# GSM_GPS.net
KiCad netlist of a schematic drawn in Altium Designer
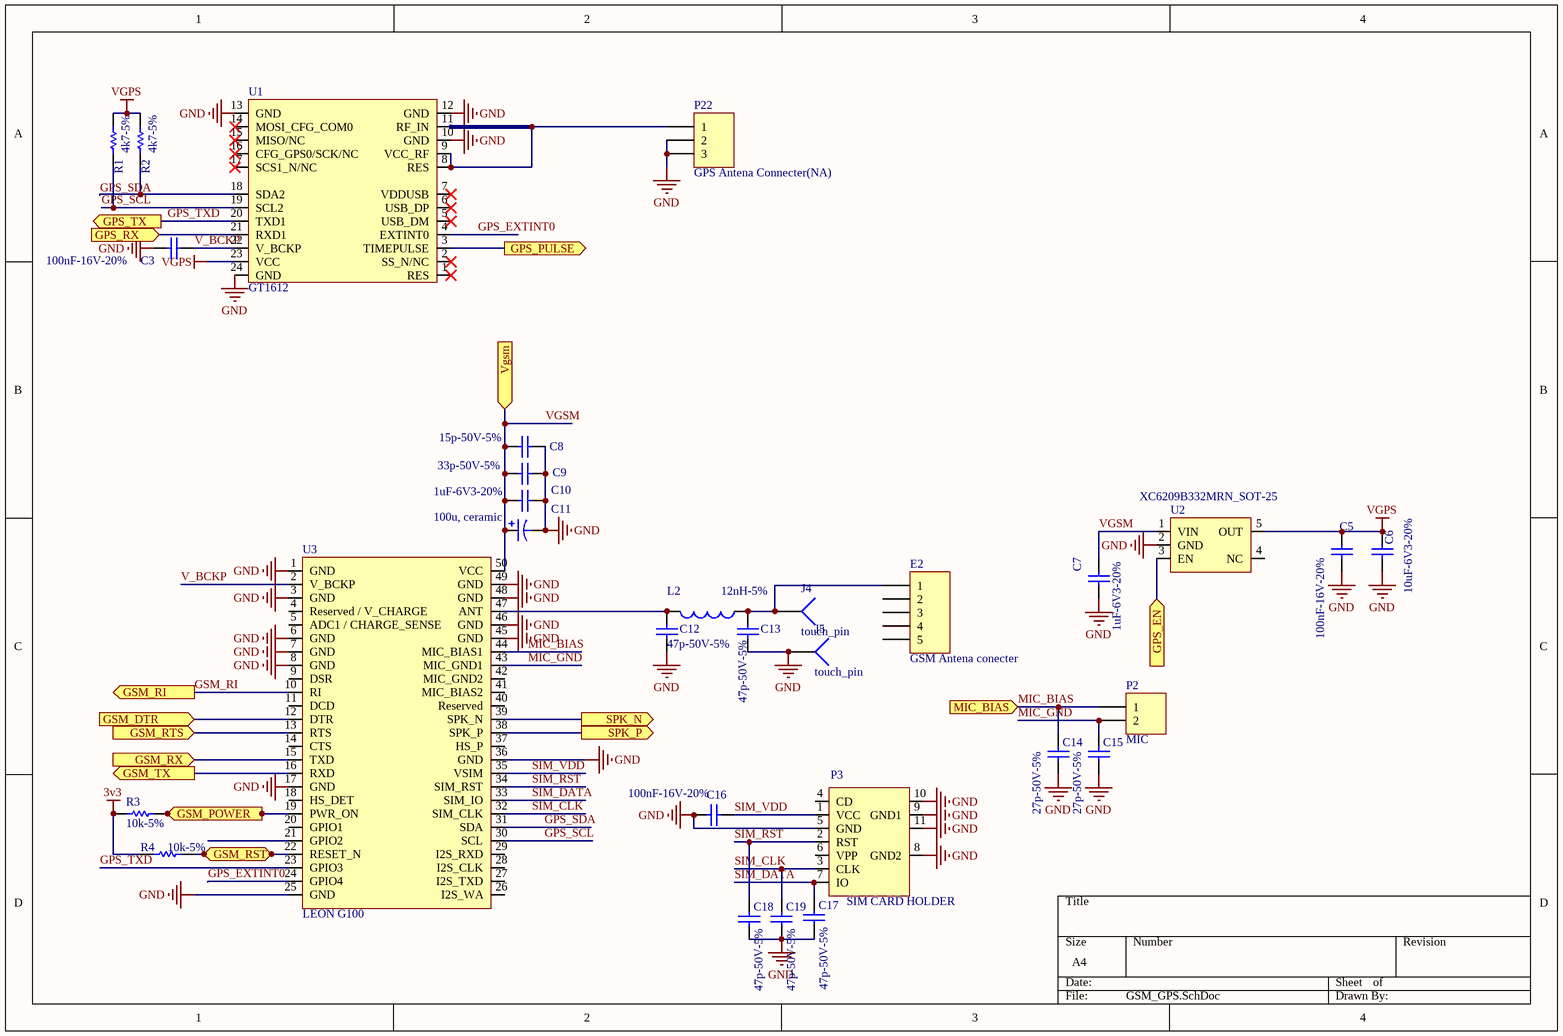
[diagram p0: GSM_GPS.SchDoc]

(export (version "E")
  (design (tool "Eeschema 10.0.6"))
  (components
    (comp (ref "C3")
      (value "100nF-16V-20%")
      (footprint "C0402")
      (description "CAP CER 0.1UF 16V Y5V 0402")
      (fields
        (field (name "MANUFACTURER") "Yageo")
        (field (name "DIGI-KEY PART NUMBER") "311-1047-1-ND")
        (field (name "PUBLISHER") "Altium Limited")
      )
      (libsource (lib "Miscellaneous Devices") (part "Cap"))
    )
    (comp (ref "C5")
      (value "100nF-16V-20%")
      (footprint "C0402")
      (description "CAP CER 0.1UF 16V Y5V 0402")
      (fields
        (field (name "MANUFACTURER") "Yageo")
        (field (name "DIGI-KEY PART NUMBER") "311-1047-1-ND")
        (field (name "PUBLISHER") "Altium Limited")
      )
      (libsource (lib "Miscellaneous Devices") (part "Cap"))
    )
    (comp (ref "C6")
      (value "10uF-6V3-20%")
      (footprint "C0603")
      (description "CAP CER 10UF 6.3V 20% X5R 0603")
      (fields
        (field (name "MANUFACTURER") "Murata Electronics North America")
        (field (name "DIGI-KEY PART NUMBER") "490-3896-1-ND")
        (field (name "PUBLISHER") "Altium Limited")
      )
      (libsource (lib "Miscellaneous Devices") (part "Cap"))
    )
    (comp (ref "C7")
      (value "1uF-6V3-20%")
      (footprint "C0402")
      (description "CAP CER 1UF 6.3V Y5V 0402")
      (fields
        (field (name "MANUFACTURER") "Yageo")
        (field (name "DIGI-KEY PART NUMBER") "311-1377-2-ND")
        (field (name "PUBLISHER") "Altium Limited")
      )
      (libsource (lib "Miscellaneous Devices") (part "Cap"))
    )
    (comp (ref "C8")
      (value "15p-50V-5%")
      (footprint "C0402")
      (description "CAP CER 15PF 50V 5% NPO 0402")
      (fields
        (field (name "MANUFACTURER") "Yageo")
        (field (name "DIGI-KEY PART NUMBER") "311-1017-1-ND")
        (field (name "PUBLISHER") "Altium Limited")
      )
      (libsource (lib "Miscellaneous Devices") (part "Cap"))
    )
    (comp (ref "C9")
      (value "33p-50V-5%")
      (footprint "C0402")
      (description "CAP CER 33PF 50V 5% NPO 0402")
      (fields
        (field (name "MANUFACTURER") "Yageo")
        (field (name "DIGI-KEY PART NUMBER") "311-1020-1-ND")
        (field (name "PUBLISHER") "Altium Limited")
      )
      (libsource (lib "Miscellaneous Devices") (part "Cap"))
    )
    (comp (ref "C10")
      (value "1uF-6V3-20%")
      (footprint "C0402")
      (description "CAP CER 1UF 6.3V Y5V 0402")
      (fields
        (field (name "MANUFACTURER") "Yageo")
        (field (name "DIGI-KEY PART NUMBER") "311-1377-2-ND")
        (field (name "PUBLISHER") "Altium Limited")
      )
      (libsource (lib "Miscellaneous Devices") (part "Cap"))
    )
    (comp (ref "C11")
      (value "100u, ceramic")
      (footprint "C1210")
      (description "CAP CER 100UF 10V 20% X5R 1812")
      (fields
        (field (name "DIGI-KEY PART NUMBER") "445-7743-2-ND")
        (field (name "MANUFACTURER PART NUMBER") "C4532X5R1A107M")
        (field (name "PUBLISHER") "Altium Limited")
      )
      (libsource (lib "Miscellaneous Devices") (part "Cap Pol3"))
    )
    (comp (ref "C12")
      (value "47p-50V-5%")
      (footprint "C0402")
      (description "CAP CER 47PF 50V 5% NPO 0402")
      (fields
        (field (name "MANUFACTURER") "Yageo")
        (field (name "DIGI-KEY PART NUMBER") "311-1021-1-ND")
        (field (name "PUBLISHER") "Altium Limited")
      )
      (libsource (lib "Miscellaneous Devices") (part "Cap"))
    )
    (comp (ref "C13")
      (value "47p-50V-5%")
      (footprint "C0402")
      (description "CAP CER 47PF 50V 5% NPO 0402")
      (fields
        (field (name "MANUFACTURER") "Yageo")
        (field (name "DIGI-KEY PART NUMBER") "311-1021-1-ND")
        (field (name "PUBLISHER") "Altium Limited")
      )
      (libsource (lib "Miscellaneous Devices") (part "Cap"))
    )
    (comp (ref "C14")
      (value "27p-50V-5%")
      (footprint "C0402")
      (description "CAP CER 27PF 50V 5% NPO 0402")
      (fields
        (field (name "MANUFACTURER") "Yageo")
        (field (name "DIGI-KEY PART NUMBER") "311-1019-2-ND")
        (field (name "PUBLISHER") "Altium Limited")
      )
      (libsource (lib "Miscellaneous Devices") (part "Cap"))
    )
    (comp (ref "C15")
      (value "27p-50V-5%")
      (footprint "C0402")
      (description "CAP CER 27PF 50V 5% NPO 0402")
      (fields
        (field (name "MANUFACTURER") "Yageo")
        (field (name "DIGI-KEY PART NUMBER") "311-1019-2-ND")
        (field (name "PUBLISHER") "Altium Limited")
      )
      (libsource (lib "Miscellaneous Devices") (part "Cap"))
    )
    (comp (ref "C16")
      (value "100nF-16V-20%")
      (footprint "C0402")
      (description "CAP CER 0.1UF 16V Y5V 0402")
      (fields
        (field (name "MANUFACTURER") "Yageo")
        (field (name "DIGI-KEY PART NUMBER") "311-1047-1-ND")
        (field (name "PUBLISHER") "Altium Limited")
      )
      (libsource (lib "Miscellaneous Devices") (part "Cap"))
    )
    (comp (ref "C17")
      (value "47p-50V-5%")
      (footprint "C0402")
      (description "CAP CER 47PF 50V 5% NPO 0402")
      (fields
        (field (name "MANUFACTURER") "Yageo")
        (field (name "DIGI-KEY PART NUMBER") "311-1021-1-ND")
        (field (name "PUBLISHER") "Altium Limited")
      )
      (libsource (lib "Miscellaneous Devices") (part "Cap"))
    )
    (comp (ref "C18")
      (value "47p-50V-5%")
      (footprint "C0402")
      (description "CAP CER 47PF 50V 5% NPO 0402")
      (fields
        (field (name "MANUFACTURER") "Yageo")
        (field (name "DIGI-KEY PART NUMBER") "311-1021-1-ND")
        (field (name "PUBLISHER") "Altium Limited")
      )
      (libsource (lib "Miscellaneous Devices") (part "Cap"))
    )
    (comp (ref "C19")
      (value "47p-50V-5%")
      (footprint "C0402")
      (description "CAP CER 47PF 50V 5% NPO 0402")
      (fields
        (field (name "MANUFACTURER") "Yageo")
        (field (name "DIGI-KEY PART NUMBER") "311-1021-1-ND")
        (field (name "PUBLISHER") "Altium Limited")
      )
      (libsource (lib "Miscellaneous Devices") (part "Cap"))
    )
    (comp (ref "E2")
      (value "GSM Antena conecter")
      (footprint "A10343-GSM850/900/1800/1900/WCDMA")
      (description "Header, 5-Pin")
      (fields (field (name "PUBLISHER") "Altium Limited"))
      (libsource (lib "Miscellaneous Connectors") (part "Header 5"))
    )
    (comp (ref "J4")
      (value "touch_pin")
      (footprint "TOUCH_PIN")
      (description "Socket")
      (fields (field (name "PUBLISHER") "Altium Limited"))
      (libsource (lib "Miscellaneous Connectors") (part "Socket"))
    )
    (comp (ref "J5")
      (value "touch_pin")
      (footprint "TOUCH_PIN")
      (description "Socket")
      (fields (field (name "PUBLISHER") "Altium Limited"))
      (libsource (lib "Miscellaneous Connectors") (part "Socket"))
    )
    (comp (ref "L2")
      (value "12nH-5%")
      (footprint "R0402")
      (description "INDUCTOR 12NH 300MA 0402")
      (fields
        (field (name "DIGI-KEY PART NUMBER") "490-2624-2-ND")
        (field (name "MANUFACTURER") "Murata Electronics North America")
        (field (name "PUBLISHER") "Altium Limited")
      )
      (libsource (lib "Miscellaneous Devices") (part "Inductor"))
    )
    (comp (ref "P2")
      (value "MIC")
      (footprint "HEADER_1.27mm_2PIN")
      (description "Header, 2-Pin")
      (fields (field (name "PUBLISHER") "Altium Limited"))
      (libsource (lib "Miscellaneous Connectors") (part "Header 2"))
    )
    (comp (ref "P3")
      (value "SIM CARD HOLDER")
      (footprint "MICRO_SIM_SOCKET")
      (description "SIM _CONNECTOR_410108105011-2LF")
      (fields (field (name "MANUFACTURER") "Tyrone"))
      (libsource (lib "Schlib1") (part "SIM CARD"))
    )
    (comp (ref "P22")
      (value "GPS Antena Connecter(NA)")
      (footprint "IPX SMD PCB Plug")
      (description "GPS Antena")
      (fields (field (name "PUBLISHER") "Altium Limited"))
      (libsource (lib "Miscellaneous Connectors") (part "Header 3"))
    )
    (comp (ref "R1")
      (value "4k7-5%")
      (footprint "R0402")
      (description "RES 4.7K OHM 1/16W 5% 0402 SMD")
      (fields
        (field (name "DIGI-KEY PART NUMBER") "311-4.7KJRCT-ND")
        (field (name "MANUFACTURER") "Yageo")
        (field (name "PUBLISHER") "Altium Limited")
      )
      (libsource (lib "Miscellaneous Devices") (part "Res1"))
    )
    (comp (ref "R2")
      (value "4k7-5%")
      (footprint "R0402")
      (description "RES 4.7K OHM 1/16W 5% 0402 SMD")
      (fields
        (field (name "DIGI-KEY PART NUMBER") "311-4.7KJRCT-ND")
        (field (name "MANUFACTURER") "Yageo")
        (field (name "PUBLISHER") "Altium Limited")
      )
      (libsource (lib "Miscellaneous Devices") (part "Res1"))
    )
    (comp (ref "R3")
      (value "10k-5%")
      (footprint "R0402")
      (description "RES 10K OHM 1/16W 5% 0402 SMD")
      (fields
        (field (name "DIGI-KEY PART NUMBER") "311-10KJRCT-ND")
        (field (name "MANUFACTURER") "Yageo")
        (field (name "PUBLISHER") "Altium Limited")
      )
      (libsource (lib "Miscellaneous Devices") (part "Res1"))
    )
    (comp (ref "R4")
      (value "10k-5%")
      (footprint "R0402")
      (description "RES 10K OHM 1/16W 5% 0402 SMD")
      (fields
        (field (name "DIGI-KEY PART NUMBER") "311-10KJRCT-ND")
        (field (name "MANUFACTURER") "Yageo")
        (field (name "PUBLISHER") "Altium Limited")
      )
      (libsource (lib "Miscellaneous Devices") (part "Res1"))
    )
    (comp (ref "U1") (value "GT1612") (footprint "GT1612") (libsource (lib "Schlib1") (part "GPS-GT1612")))
    (comp (ref "U2")
      (value "XC6209B332MRN_SOT-25")
      (footprint "SOT23-5")
      (fields (field (name "MANUFACTURER") "Tyrone"))
      (libsource (lib "Schlib1") (part "XC6209B332MRN_SOT-25"))
    )
    (comp (ref "U3")
      (value "LEON G100")
      (footprint "U-BLOX-G100")
      (fields (field (name "MANUFACTURER") "Tyrone"))
      (libsource (lib "gsm_module") (part "ublox"))
    )
  )
  (nets
    (net (code "1") (name "/GPS_EN") (class "Default")
      (node (ref "U2") (pin "3") (pinfunction "EN_3") (pintype "passive"))
    )
    (net (code "2") (name "/GPS_EXTINT0") (class "Default")
      (node (ref "U1") (pin "4") (pinfunction "EXTINT0_4") (pintype "passive"))
      (node (ref "U3") (pin "24") (pinfunction "GPIO4_24") (pintype "passive"))
    )
    (net (code "3") (name "/GPS_PULSE") (class "Default")
      (node (ref "U1") (pin "3") (pinfunction "TIMEPULSE_3") (pintype "passive"))
    )
    (net (code "4") (name "/GPS_RX") (class "Default")
      (node (ref "U1") (pin "21") (pinfunction "RXD1_21") (pintype "passive"))
    )
    (net (code "5") (name "/GPS_SCL") (class "Default")
      (node (ref "R1") (pin "1") (pinfunction "1_1") (pintype "passive"))
      (node (ref "U1") (pin "19") (pinfunction "SCL2_19") (pintype "passive"))
      (node (ref "U3") (pin "30") (pinfunction "SCL_30") (pintype "passive"))
    )
    (net (code "6") (name "/GPS_SDA") (class "Default")
      (node (ref "R2") (pin "1") (pinfunction "1_1") (pintype "passive"))
      (node (ref "U1") (pin "18") (pinfunction "SDA2_18") (pintype "passive"))
      (node (ref "U3") (pin "31") (pinfunction "SDA_31") (pintype "passive"))
    )
    (net (code "7") (name "/GPS_TXD") (class "Default")
      (node (ref "U1") (pin "20") (pinfunction "TXD1_20") (pintype "passive"))
      (node (ref "U3") (pin "23") (pinfunction "GPIO3_23") (pintype "passive"))
    )
    (net (code "8") (name "/GSM_DTR") (class "Default")
      (node (ref "U3") (pin "12") (pinfunction "DTR_12") (pintype "passive"))
    )
    (net (code "9") (name "/GSM_POWER") (class "Default")
      (node (ref "R3") (pin "2") (pinfunction "2_2") (pintype "passive"))
      (node (ref "U3") (pin "19") (pinfunction "PWR_ON_19") (pintype "passive"))
    )
    (net (code "10") (name "/GSM_RI") (class "Default")
      (node (ref "U3") (pin "10") (pinfunction "RI_10") (pintype "passive"))
    )
    (net (code "11") (name "/GSM_RST") (class "Default")
      (node (ref "R4") (pin "2") (pinfunction "2_2") (pintype "passive"))
      (node (ref "U3") (pin "22") (pinfunction "RESET_N_22") (pintype "passive"))
    )
    (net (code "12") (name "/GSM_RTS") (class "Default")
      (node (ref "U3") (pin "13") (pinfunction "RTS_13") (pintype "passive"))
    )
    (net (code "13") (name "/GSM_RX") (class "Default")
      (node (ref "U3") (pin "15") (pinfunction "TXD_15") (pintype "passive"))
    )
    (net (code "14") (name "/GSM_TX") (class "Default")
      (node (ref "U3") (pin "16") (pinfunction "RXD_16") (pintype "passive"))
    )
    (net (code "15") (name "/MIC_BIAS") (class "Default")
      (node (ref "C14") (pin "2") (pinfunction "2_2") (pintype "passive"))
      (node (ref "P2") (pin "1") (pinfunction "1_1") (pintype "passive"))
      (node (ref "U3") (pin "44") (pinfunction "MIC_BIAS1_44") (pintype "passive"))
    )
    (net (code "16") (name "/MIC_GND") (class "Default")
      (node (ref "C15") (pin "2") (pinfunction "2_2") (pintype "passive"))
      (node (ref "P2") (pin "2") (pinfunction "2_2") (pintype "passive"))
      (node (ref "U3") (pin "43") (pinfunction "MIC_GND1_43") (pintype "passive"))
    )
    (net (code "17") (name "/SIM_CLK") (class "Default")
      (node (ref "C19") (pin "2") (pinfunction "2_2") (pintype "passive"))
      (node (ref "P3") (pin "3") (pinfunction "CLK_3") (pintype "passive"))
      (node (ref "U3") (pin "32") (pinfunction "SIM_CLK_32") (pintype "passive"))
    )
    (net (code "18") (name "/SIM_DATA") (class "Default")
      (node (ref "C17") (pin "2") (pinfunction "2_2") (pintype "passive"))
      (node (ref "P3") (pin "7") (pinfunction "IO_7") (pintype "passive"))
      (node (ref "U3") (pin "33") (pinfunction "SIM_IO_33") (pintype "passive"))
    )
    (net (code "19") (name "/SIM_RST") (class "Default")
      (node (ref "C18") (pin "2") (pinfunction "2_2") (pintype "passive"))
      (node (ref "P3") (pin "2") (pinfunction "RST_2") (pintype "passive"))
      (node (ref "U3") (pin "34") (pinfunction "SIM_RST_34") (pintype "passive"))
    )
    (net (code "20") (name "/SIM_VDD") (class "Default")
      (node (ref "C16") (pin "1") (pinfunction "1_1") (pintype "passive"))
      (node (ref "P3") (pin "1") (pinfunction "VCC_1") (pintype "passive"))
      (node (ref "U3") (pin "35") (pinfunction "VSIM_35") (pintype "passive"))
    )
    (net (code "21") (name "/SPK_N") (class "Default")
      (node (ref "U3") (pin "39") (pinfunction "SPK_N_39") (pintype "passive"))
    )
    (net (code "22") (name "/SPK_P") (class "Default")
      (node (ref "U3") (pin "38") (pinfunction "SPK_P_38") (pintype "passive"))
    )
    (net (code "23") (name "/VGSM") (class "Default")
      (node (ref "C10") (pin "2") (pinfunction "2_2") (pintype "passive"))
      (node (ref "C11") (pin "1") (pinfunction "1_1") (pintype "passive"))
      (node (ref "C7") (pin "2") (pinfunction "2_2") (pintype "passive"))
      (node (ref "C8") (pin "1") (pinfunction "1_1") (pintype "passive"))
      (node (ref "C9") (pin "1") (pinfunction "1_1") (pintype "passive"))
      (node (ref "U2") (pin "1") (pinfunction "VIN_1") (pintype "passive"))
      (node (ref "U3") (pin "50") (pinfunction "VCC_50") (pintype "passive"))
    )
    (net (code "24") (name "/V_BCKP") (class "Default")
      (node (ref "C3") (pin "2") (pinfunction "2_2") (pintype "passive"))
      (node (ref "U1") (pin "22") (pinfunction "V_BCKP_22") (pintype "passive"))
      (node (ref "U3") (pin "2") (pinfunction "V_BCKP_2") (pintype "passive"))
    )
    (net (code "25") (name "3v3") (class "Default")
      (node (ref "R3") (pin "1") (pinfunction "1_1") (pintype "passive"))
      (node (ref "R4") (pin "1") (pinfunction "1_1") (pintype "passive"))
    )
    (net (code "26") (name "GND") (class "Default")
      (node (ref "C10") (pin "1") (pinfunction "1_1") (pintype "passive"))
      (node (ref "C11") (pin "2") (pinfunction "2_2") (pintype "passive"))
      (node (ref "C12") (pin "1") (pinfunction "1_1") (pintype "passive"))
      (node (ref "C13") (pin "1") (pinfunction "1_1") (pintype "passive"))
      (node (ref "C14") (pin "1") (pinfunction "1_1") (pintype "passive"))
      (node (ref "C15") (pin "1") (pinfunction "1_1") (pintype "passive"))
      (node (ref "C16") (pin "2") (pinfunction "2_2") (pintype "passive"))
      (node (ref "C17") (pin "1") (pinfunction "1_1") (pintype "passive"))
      (node (ref "C18") (pin "1") (pinfunction "1_1") (pintype "passive"))
      (node (ref "C19") (pin "1") (pinfunction "1_1") (pintype "passive"))
      (node (ref "C3") (pin "1") (pinfunction "1_1") (pintype "passive"))
      (node (ref "C5") (pin "1") (pinfunction "1_1") (pintype "passive"))
      (node (ref "C6") (pin "1") (pinfunction "1_1") (pintype "passive"))
      (node (ref "C7") (pin "1") (pinfunction "1_1") (pintype "passive"))
      (node (ref "C8") (pin "2") (pinfunction "2_2") (pintype "passive"))
      (node (ref "C9") (pin "2") (pinfunction "2_2") (pintype "passive"))
      (node (ref "J5") (pin "1") (pinfunction "1_1") (pintype "passive"))
      (node (ref "P22") (pin "2") (pinfunction "2_2") (pintype "passive"))
      (node (ref "P22") (pin "3") (pinfunction "3_3") (pintype "passive"))
      (node (ref "P3") (pin "10") (pinfunction "GND3_10") (pintype "passive"))
      (node (ref "P3") (pin "11") (pinfunction "GND4_11") (pintype "passive"))
      (node (ref "P3") (pin "5") (pinfunction "GND_5") (pintype "passive"))
      (node (ref "P3") (pin "8") (pinfunction "GND2_8") (pintype "passive"))
      (node (ref "P3") (pin "9") (pinfunction "GND1_9") (pintype "passive"))
      (node (ref "U1") (pin "10") (pinfunction "GND_10") (pintype "passive"))
      (node (ref "U1") (pin "12") (pinfunction "GND_12") (pintype "passive"))
      (node (ref "U1") (pin "13") (pinfunction "GND_13") (pintype "passive"))
      (node (ref "U1") (pin "24") (pinfunction "GND_24") (pintype "passive"))
      (node (ref "U2") (pin "2") (pinfunction "GND_2") (pintype "passive"))
      (node (ref "U3") (pin "1") (pinfunction "GND_1") (pintype "passive"))
      (node (ref "U3") (pin "17") (pinfunction "GND_17") (pintype "passive"))
      (node (ref "U3") (pin "25") (pinfunction "GND_25") (pintype "passive"))
      (node (ref "U3") (pin "3") (pinfunction "GND_3") (pintype "passive"))
      (node (ref "U3") (pin "36") (pinfunction "GND_36") (pintype "passive"))
      (node (ref "U3") (pin "45") (pinfunction "GND_45") (pintype "passive"))
      (node (ref "U3") (pin "46") (pinfunction "GND_46") (pintype "passive"))
      (node (ref "U3") (pin "48") (pinfunction "GND_48") (pintype "passive"))
      (node (ref "U3") (pin "49") (pinfunction "GND_49") (pintype "passive"))
      (node (ref "U3") (pin "6") (pinfunction "GND_6") (pintype "passive"))
      (node (ref "U3") (pin "7") (pinfunction "GND_7") (pintype "passive"))
      (node (ref "U3") (pin "8") (pinfunction "GND_8") (pintype "passive"))
    )
    (net (code "27") (name "Net-(C13-Pad2)") (class "Default")
      (node (ref "C13") (pin "2") (pinfunction "2_2") (pintype "passive"))
      (node (ref "E2") (pin "1") (pinfunction "1_1") (pintype "passive"))
      (node (ref "J4") (pin "1") (pinfunction "1_1") (pintype "passive"))
      (node (ref "L2") (pin "1") (pinfunction "1_1") (pintype "passive"))
    )
    (net (code "28") (name "Net-(U1-RF_IN)") (class "Default")
      (node (ref "P22") (pin "1") (pinfunction "1_1") (pintype "passive"))
      (node (ref "U1") (pin "11") (pinfunction "RF_IN_11") (pintype "passive"))
      (node (ref "U1") (pin "8") (pinfunction "RES_8") (pintype "passive"))
      (node (ref "U1") (pin "9") (pinfunction "VCC_RF_9") (pintype "passive"))
    )
    (net (code "29") (name "Net-(U3-ANT)") (class "Default")
      (node (ref "C12") (pin "2") (pinfunction "2_2") (pintype "passive"))
      (node (ref "L2") (pin "2") (pinfunction "2_2") (pintype "passive"))
      (node (ref "U3") (pin "47") (pinfunction "ANT_47") (pintype "passive"))
    )
    (net (code "30") (name "VGPS") (class "Default")
      (node (ref "C5") (pin "2") (pinfunction "2_2") (pintype "passive"))
      (node (ref "C6") (pin "2") (pinfunction "2_2") (pintype "passive"))
      (node (ref "R1") (pin "2") (pinfunction "2_2") (pintype "passive"))
      (node (ref "R2") (pin "2") (pinfunction "2_2") (pintype "passive"))
      (node (ref "U1") (pin "23") (pinfunction "VCC_23") (pintype "passive"))
      (node (ref "U2") (pin "5") (pinfunction "OUT_5") (pintype "passive"))
    )
    (net (code "31") (name "unconnected-(E2-Pad2)") (class "Default")
      (node (ref "E2") (pin "2") (pinfunction "2_2") (pintype "passive"))
    )
    (net (code "32") (name "unconnected-(E2-Pad3)") (class "Default")
      (node (ref "E2") (pin "3") (pinfunction "3_3") (pintype "passive"))
    )
    (net (code "33") (name "unconnected-(E2-Pad4)") (class "Default")
      (node (ref "E2") (pin "4") (pinfunction "4_4") (pintype "passive"))
    )
    (net (code "34") (name "unconnected-(E2-Pad5)") (class "Default")
      (node (ref "E2") (pin "5") (pinfunction "5_5") (pintype "passive"))
    )
    (net (code "35") (name "unconnected-(P3-CD-Pad4)") (class "Default")
      (node (ref "P3") (pin "4") (pinfunction "CD_4") (pintype "passive"))
    )
    (net (code "36") (name "unconnected-(P3-VPP-Pad6)") (class "Default")
      (node (ref "P3") (pin "6") (pinfunction "VPP_6") (pintype "passive"))
    )
    (net (code "37") (name "unconnected-(U1-CFG_GPS0{slash}SCK{slash}NC-Pad16)") (class "Default")
      (node (ref "U1") (pin "16") (pinfunction "CFG_GPS0/SCK/NC_16") (pintype "passive+no_connect"))
    )
    (net (code "38") (name "unconnected-(U1-MISO{slash}NC-Pad15)") (class "Default")
      (node (ref "U1") (pin "15") (pinfunction "MISO/NC_15") (pintype "passive+no_connect"))
    )
    (net (code "39") (name "unconnected-(U1-MOSI_CFG_COM0-Pad14)") (class "Default")
      (node (ref "U1") (pin "14") (pinfunction "MOSI_CFG_COM0_14") (pintype "passive+no_connect"))
    )
    (net (code "40") (name "unconnected-(U1-RES-Pad1)") (class "Default")
      (node (ref "U1") (pin "1") (pinfunction "RES_1") (pintype "passive+no_connect"))
    )
    (net (code "41") (name "unconnected-(U1-SCS1_N{slash}NC-Pad17)") (class "Default")
      (node (ref "U1") (pin "17") (pinfunction "SCS1_N/NC_17") (pintype "passive+no_connect"))
    )
    (net (code "42") (name "unconnected-(U1-SS_N{slash}NC-Pad2)") (class "Default")
      (node (ref "U1") (pin "2") (pinfunction "SS_N/NC_2") (pintype "passive+no_connect"))
    )
    (net (code "43") (name "unconnected-(U1-USB_DM-Pad5)") (class "Default")
      (node (ref "U1") (pin "5") (pinfunction "USB_DM_5") (pintype "passive+no_connect"))
    )
    (net (code "44") (name "unconnected-(U1-USB_DP-Pad6)") (class "Default")
      (node (ref "U1") (pin "6") (pinfunction "USB_DP_6") (pintype "passive+no_connect"))
    )
    (net (code "45") (name "unconnected-(U1-VDDUSB-Pad7)") (class "Default")
      (node (ref "U1") (pin "7") (pinfunction "VDDUSB_7") (pintype "passive+no_connect"))
    )
    (net (code "46") (name "unconnected-(U2-NC-Pad4)") (class "Default")
      (node (ref "U2") (pin "4") (pinfunction "NC_4") (pintype "passive"))
    )
    (net (code "47") (name "unconnected-(U3-ADC1_{slash}_CHARGE_SENSE-Pad5)") (class "Default")
      (node (ref "U3") (pin "5") (pinfunction "ADC1_/_CHARGE_SENSE_5") (pintype "passive"))
    )
    (net (code "48") (name "unconnected-(U3-CTS-Pad14)") (class "Default")
      (node (ref "U3") (pin "14") (pinfunction "CTS_14") (pintype "passive"))
    )
    (net (code "49") (name "unconnected-(U3-DCD-Pad11)") (class "Default")
      (node (ref "U3") (pin "11") (pinfunction "DCD_11") (pintype "passive"))
    )
    (net (code "50") (name "unconnected-(U3-DSR-Pad9)") (class "Default")
      (node (ref "U3") (pin "9") (pinfunction "DSR_9") (pintype "passive"))
    )
    (net (code "51") (name "unconnected-(U3-GPIO1-Pad20)") (class "Default")
      (node (ref "U3") (pin "20") (pinfunction "GPIO1_20") (pintype "passive"))
    )
    (net (code "52") (name "unconnected-(U3-GPIO2-Pad21)") (class "Default")
      (node (ref "U3") (pin "21") (pinfunction "GPIO2_21") (pintype "passive"))
    )
    (net (code "53") (name "unconnected-(U3-HS_DET-Pad18)") (class "Default")
      (node (ref "U3") (pin "18") (pinfunction "HS_DET_18") (pintype "passive"))
    )
    (net (code "54") (name "unconnected-(U3-HS_P-Pad37)") (class "Default")
      (node (ref "U3") (pin "37") (pinfunction "HS_P_37") (pintype "passive"))
    )
    (net (code "55") (name "unconnected-(U3-I2S_CLK-Pad28)") (class "Default")
      (node (ref "U3") (pin "28") (pinfunction "I2S_CLK_28") (pintype "passive"))
    )
    (net (code "56") (name "unconnected-(U3-I2S_RXD-Pad29)") (class "Default")
      (node (ref "U3") (pin "29") (pinfunction "I2S_RXD_29") (pintype "passive"))
    )
    (net (code "57") (name "unconnected-(U3-I2S_TXD-Pad27)") (class "Default")
      (node (ref "U3") (pin "27") (pinfunction "I2S_TXD_27") (pintype "passive"))
    )
    (net (code "58") (name "unconnected-(U3-I2S_WA-Pad26)") (class "Default")
      (node (ref "U3") (pin "26") (pinfunction "I2S_WA_26") (pintype "passive"))
    )
    (net (code "59") (name "unconnected-(U3-MIC_BIAS2-Pad41)") (class "Default")
      (node (ref "U3") (pin "41") (pinfunction "MIC_BIAS2_41") (pintype "passive"))
    )
    (net (code "60") (name "unconnected-(U3-MIC_GND2-Pad42)") (class "Default")
      (node (ref "U3") (pin "42") (pinfunction "MIC_GND2_42") (pintype "passive"))
    )
    (net (code "61") (name "unconnected-(U3-Reserved-Pad40)") (class "Default")
      (node (ref "U3") (pin "40") (pinfunction "Reserved_40") (pintype "passive"))
    )
    (net (code "62") (name "unconnected-(U3-Reserved_{slash}_V_CHARGE-Pad4)") (class "Default")
      (node (ref "U3") (pin "4") (pinfunction "Reserved_/_V_CHARGE_4") (pintype "passive"))
    )
  )
)
